# 6502_BASIC.net
KiCad netlist of a schematic drawn in EAGLE
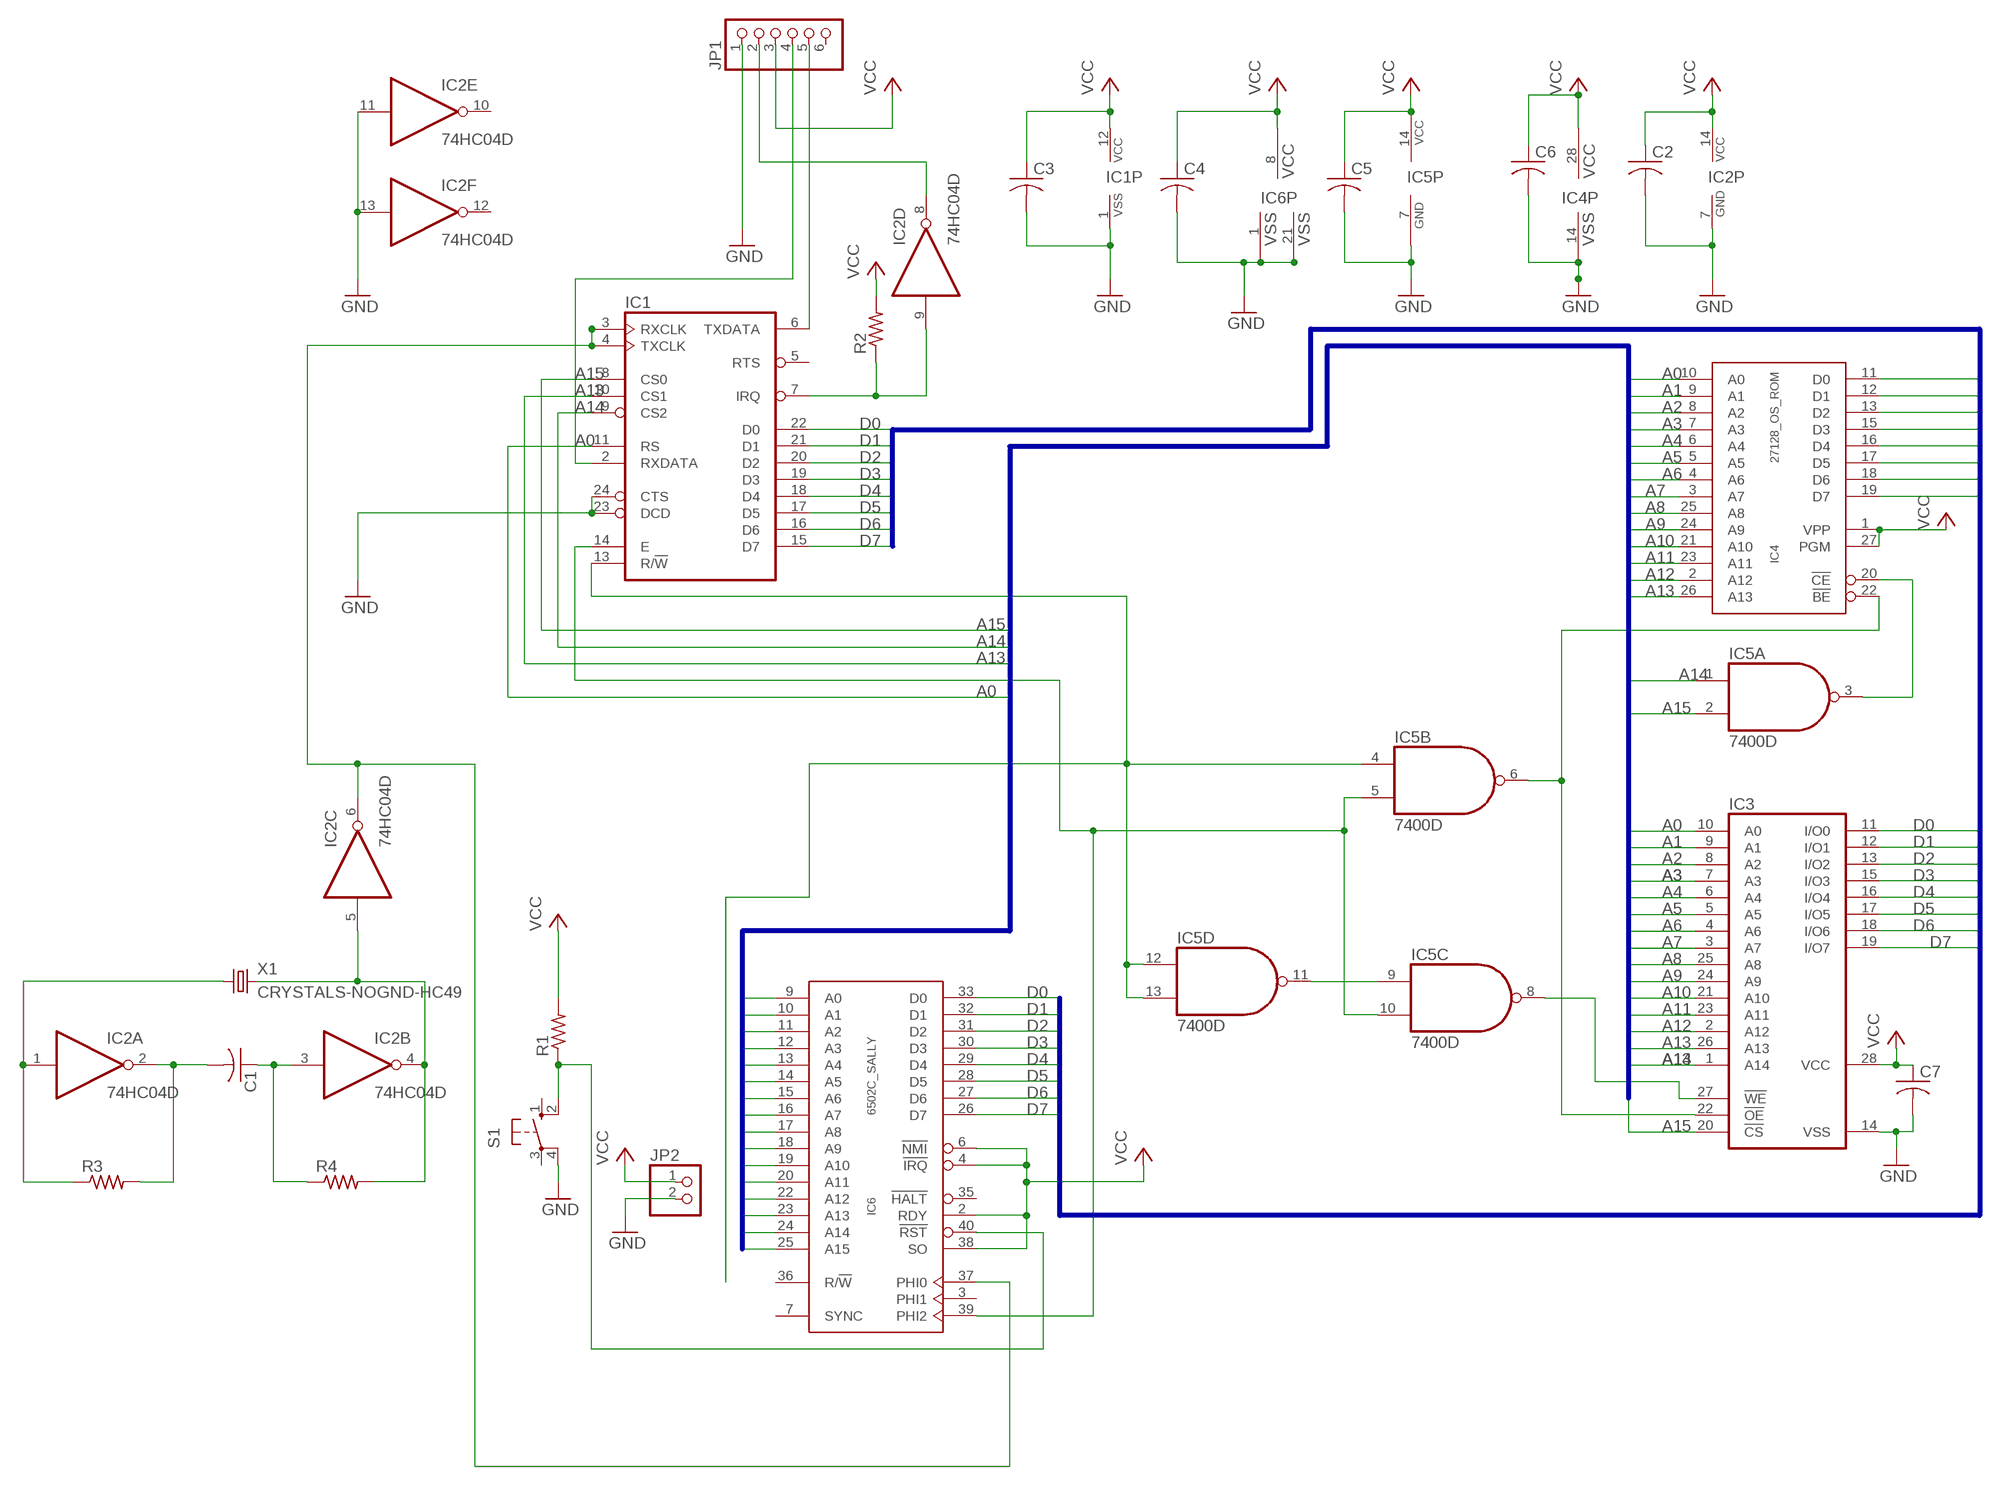
[diagram p0: schematic, sheet 1]

(export (version "E")
  (design (tool "Eeschema 10.0.6"))
  (components
    (comp (ref "C1")
      (value "C-USC1608")
      (footprint "eagle-import:C1608")
      (libsource (lib "eagle-import") (part "C-USC1608"))
    )
    (comp (ref "C2")
      (value "C-USC1608")
      (footprint "eagle-import:C1608")
      (libsource (lib "eagle-import") (part "C-USC1608"))
    )
    (comp (ref "C3")
      (value "C-USC1608")
      (footprint "eagle-import:C1608")
      (libsource (lib "eagle-import") (part "C-USC1608"))
    )
    (comp (ref "C4")
      (value "C-USC1608")
      (footprint "eagle-import:C1608")
      (libsource (lib "eagle-import") (part "C-USC1608"))
    )
    (comp (ref "C5")
      (value "C-USC1608")
      (footprint "eagle-import:C1608")
      (libsource (lib "eagle-import") (part "C-USC1608"))
    )
    (comp (ref "C6")
      (value "C-USC1608")
      (footprint "eagle-import:C1608")
      (libsource (lib "eagle-import") (part "C-USC1608"))
    )
    (comp (ref "C7")
      (value "C-USC1608")
      (footprint "eagle-import:C1608")
      (libsource (lib "eagle-import") (part "C-USC1608"))
    )
    (comp (ref "IC1")
      (value "6850")
      (footprint "eagle-import:DIL24")
      (fields (field (name "MF") "NTE ELECTRONICS") (field (name "MPN") "NTE6850"))
      (libsource (lib "eagle-import") (part "6850"))
    )
    (comp (ref "IC2")
      (value "74HC04D")
      (footprint "eagle-import:SO14")
      (libsource (lib "eagle-import") (part "7404DHC"))
    )
    (comp (ref "IC3")
      (value "62256P")
      (footprint "eagle-import:DIL28-6")
      (libsource (lib "eagle-import") (part "62256P"))
    )
    (comp (ref "IC4")
      (value "27128_OS_ROM")
      (footprint "eagle-import:DIL28")
      (libsource (lib "eagle-import") (part "27128_OS_ROM"))
    )
    (comp (ref "IC5")
      (value "7400D")
      (footprint "eagle-import:SO14")
      (libsource (lib "eagle-import") (part "7400D"))
    )
    (comp (ref "IC6")
      (value "6502C_SALLY")
      (footprint "eagle-import:DIL40")
      (libsource (lib "eagle-import") (part "6502C_SALLY"))
    )
    (comp (ref "JP1")
      (value "HEADER-1X6")
      (footprint "eagle-import:1X06_OVAL")
      (libsource (lib "eagle-import") (part "HEADER-1X6"))
    )
    (comp (ref "JP2")
      (value "HEADER-1X2")
      (footprint "eagle-import:1X02_OVAL")
      (libsource (lib "eagle-import") (part "HEADER-1X2"))
    )
    (comp (ref "R1")
      (value "R-US_R0603")
      (footprint "eagle-import:R0603")
      (libsource (lib "eagle-import") (part "R-US_R0603"))
    )
    (comp (ref "R2")
      (value "R-US_R0603")
      (footprint "eagle-import:R0603")
      (libsource (lib "eagle-import") (part "R-US_R0603"))
    )
    (comp (ref "R3")
      (value "R-US_R0603")
      (footprint "eagle-import:R0603")
      (libsource (lib "eagle-import") (part "R-US_R0603"))
    )
    (comp (ref "R4")
      (value "R-US_R0603")
      (footprint "eagle-import:R0603")
      (libsource (lib "eagle-import") (part "R-US_R0603"))
    )
    (comp (ref "S1")
      (value "10-XX")
      (footprint "eagle-import:B3F-10XX")
      (fields (field (name "MPN") "B3F-1000"))
      (libsource (lib "eagle-import") (part "10-XX"))
    )
    (comp (ref "X1")
      (value "CRYSTALS-NOGND-HC49")
      (footprint "eagle-import:HC49")
      (libsource (lib "eagle-import") (part "CRYSTALS-NOGND-HC49"))
    )
  )
  (nets
    (net (code "1") (name "/A0") (class "Default")
      (node (ref "IC1") (pin "11") (pinfunction "RS_11") (pintype "input"))
      (node (ref "IC3") (pin "10") (pinfunction "A0_10") (pintype "input"))
      (node (ref "IC4") (pin "10") (pinfunction "A0_10") (pintype "input"))
      (node (ref "IC6") (pin "9") (pinfunction "A0_9") (pintype "output"))
    )
    (net (code "2") (name "/A1") (class "Default")
      (node (ref "IC3") (pin "9") (pinfunction "A1_9") (pintype "input"))
      (node (ref "IC4") (pin "9") (pinfunction "A1_9") (pintype "input"))
      (node (ref "IC6") (pin "10") (pinfunction "A1_10") (pintype "output"))
    )
    (net (code "3") (name "/A2") (class "Default")
      (node (ref "IC3") (pin "8") (pinfunction "A2_8") (pintype "input"))
      (node (ref "IC4") (pin "8") (pinfunction "A2_8") (pintype "input"))
      (node (ref "IC6") (pin "11") (pinfunction "A2_11") (pintype "output"))
    )
    (net (code "4") (name "/A3") (class "Default")
      (node (ref "IC3") (pin "7") (pinfunction "A3_7") (pintype "input"))
      (node (ref "IC4") (pin "7") (pinfunction "A3_7") (pintype "input"))
      (node (ref "IC6") (pin "12") (pinfunction "A3_12") (pintype "output"))
    )
    (net (code "5") (name "/A4") (class "Default")
      (node (ref "IC3") (pin "6") (pinfunction "A4_6") (pintype "input"))
      (node (ref "IC4") (pin "6") (pinfunction "A4_6") (pintype "input"))
      (node (ref "IC6") (pin "13") (pinfunction "A4_13") (pintype "output"))
    )
    (net (code "6") (name "/A5") (class "Default")
      (node (ref "IC3") (pin "5") (pinfunction "A5_5") (pintype "input"))
      (node (ref "IC4") (pin "5") (pinfunction "A5_5") (pintype "input"))
      (node (ref "IC6") (pin "14") (pinfunction "A5_14") (pintype "output"))
    )
    (net (code "7") (name "/A6") (class "Default")
      (node (ref "IC3") (pin "4") (pinfunction "A6_4") (pintype "input"))
      (node (ref "IC4") (pin "4") (pinfunction "A6_4") (pintype "input"))
      (node (ref "IC6") (pin "15") (pinfunction "A6_15") (pintype "output"))
    )
    (net (code "8") (name "/A7") (class "Default")
      (node (ref "IC3") (pin "3") (pinfunction "A7_3") (pintype "input"))
      (node (ref "IC4") (pin "3") (pinfunction "A7_3") (pintype "input"))
      (node (ref "IC6") (pin "16") (pinfunction "A7_16") (pintype "output"))
    )
    (net (code "9") (name "/A8") (class "Default")
      (node (ref "IC3") (pin "25") (pinfunction "A8_25") (pintype "input"))
      (node (ref "IC4") (pin "25") (pinfunction "A8_25") (pintype "input"))
      (node (ref "IC6") (pin "17") (pinfunction "A8_17") (pintype "output"))
    )
    (net (code "10") (name "/A9") (class "Default")
      (node (ref "IC3") (pin "24") (pinfunction "A9_24") (pintype "input"))
      (node (ref "IC4") (pin "24") (pinfunction "A9_24") (pintype "input"))
      (node (ref "IC6") (pin "18") (pinfunction "A9_18") (pintype "output"))
    )
    (net (code "11") (name "/A10") (class "Default")
      (node (ref "IC3") (pin "21") (pinfunction "A10_21") (pintype "input"))
      (node (ref "IC4") (pin "21") (pinfunction "A10_21") (pintype "input"))
      (node (ref "IC6") (pin "19") (pinfunction "A10_19") (pintype "output"))
    )
    (net (code "12") (name "/A11") (class "Default")
      (node (ref "IC3") (pin "23") (pinfunction "A11_23") (pintype "input"))
      (node (ref "IC4") (pin "23") (pinfunction "A11_23") (pintype "input"))
      (node (ref "IC6") (pin "20") (pinfunction "A11_20") (pintype "output"))
    )
    (net (code "13") (name "/A12") (class "Default")
      (node (ref "IC3") (pin "2") (pinfunction "A12_2") (pintype "input"))
      (node (ref "IC4") (pin "2") (pinfunction "A12_2") (pintype "input"))
      (node (ref "IC6") (pin "22") (pinfunction "A12_22") (pintype "output"))
    )
    (net (code "14") (name "/A13") (class "Default")
      (node (ref "IC1") (pin "10") (pinfunction "CS1_10") (pintype "input"))
      (node (ref "IC3") (pin "26") (pinfunction "A13_26") (pintype "input"))
      (node (ref "IC4") (pin "26") (pinfunction "A13_26") (pintype "input"))
      (node (ref "IC6") (pin "23") (pinfunction "A13_23") (pintype "output"))
    )
    (net (code "15") (name "/A14") (class "Default")
      (node (ref "IC1") (pin "9") (pinfunction "CS2_9") (pintype "input"))
      (node (ref "IC3") (pin "1") (pinfunction "A14_1") (pintype "input"))
      (node (ref "IC5") (pin "1") (pinfunction "I0_1") (pintype "input"))
      (node (ref "IC6") (pin "24") (pinfunction "A14_24") (pintype "output"))
    )
    (net (code "16") (name "/A15") (class "Default")
      (node (ref "IC1") (pin "8") (pinfunction "CS0_8") (pintype "input"))
      (node (ref "IC3") (pin "20") (pinfunction "~{CS}_20") (pintype "input"))
      (node (ref "IC5") (pin "2") (pinfunction "I1_2") (pintype "input"))
      (node (ref "IC6") (pin "25") (pinfunction "A15_25") (pintype "output"))
    )
    (net (code "17") (name "/D0") (class "Default")
      (node (ref "IC1") (pin "22") (pinfunction "D0_22") (pintype "bidirectional"))
      (node (ref "IC3") (pin "11") (pinfunction "I/O0_11") (pintype "bidirectional"))
      (node (ref "IC4") (pin "11") (pinfunction "D0_11") (pintype "output"))
      (node (ref "IC6") (pin "33") (pinfunction "D0_33") (pintype "bidirectional"))
    )
    (net (code "18") (name "/D1") (class "Default")
      (node (ref "IC1") (pin "21") (pinfunction "D1_21") (pintype "bidirectional"))
      (node (ref "IC3") (pin "12") (pinfunction "I/O1_12") (pintype "bidirectional"))
      (node (ref "IC4") (pin "12") (pinfunction "D1_12") (pintype "output"))
      (node (ref "IC6") (pin "32") (pinfunction "D1_32") (pintype "bidirectional"))
    )
    (net (code "19") (name "/D2") (class "Default")
      (node (ref "IC1") (pin "20") (pinfunction "D2_20") (pintype "bidirectional"))
      (node (ref "IC3") (pin "13") (pinfunction "I/O2_13") (pintype "bidirectional"))
      (node (ref "IC4") (pin "13") (pinfunction "D2_13") (pintype "output"))
      (node (ref "IC6") (pin "31") (pinfunction "D2_31") (pintype "bidirectional"))
    )
    (net (code "20") (name "/D3") (class "Default")
      (node (ref "IC1") (pin "19") (pinfunction "D3_19") (pintype "bidirectional"))
      (node (ref "IC3") (pin "15") (pinfunction "I/O3_15") (pintype "bidirectional"))
      (node (ref "IC4") (pin "15") (pinfunction "D3_15") (pintype "output"))
      (node (ref "IC6") (pin "30") (pinfunction "D3_30") (pintype "bidirectional"))
    )
    (net (code "21") (name "/D4") (class "Default")
      (node (ref "IC1") (pin "18") (pinfunction "D4_18") (pintype "bidirectional"))
      (node (ref "IC3") (pin "16") (pinfunction "I/O4_16") (pintype "bidirectional"))
      (node (ref "IC4") (pin "16") (pinfunction "D4_16") (pintype "output"))
      (node (ref "IC6") (pin "29") (pinfunction "D4_29") (pintype "bidirectional"))
    )
    (net (code "22") (name "/D5") (class "Default")
      (node (ref "IC1") (pin "17") (pinfunction "D5_17") (pintype "bidirectional"))
      (node (ref "IC3") (pin "17") (pinfunction "I/O5_17") (pintype "bidirectional"))
      (node (ref "IC4") (pin "17") (pinfunction "D5_17") (pintype "output"))
      (node (ref "IC6") (pin "28") (pinfunction "D5_28") (pintype "bidirectional"))
    )
    (net (code "23") (name "/D6") (class "Default")
      (node (ref "IC1") (pin "16") (pinfunction "D6_16") (pintype "bidirectional"))
      (node (ref "IC3") (pin "18") (pinfunction "I/O6_18") (pintype "bidirectional"))
      (node (ref "IC4") (pin "18") (pinfunction "D6_18") (pintype "output"))
      (node (ref "IC6") (pin "27") (pinfunction "D6_27") (pintype "bidirectional"))
    )
    (net (code "24") (name "/D7") (class "Default")
      (node (ref "IC1") (pin "15") (pinfunction "D7_15") (pintype "bidirectional"))
      (node (ref "IC3") (pin "19") (pinfunction "I/O7_19") (pintype "bidirectional"))
      (node (ref "IC4") (pin "19") (pinfunction "D7_19") (pintype "output"))
      (node (ref "IC6") (pin "26") (pinfunction "D7_26") (pintype "bidirectional"))
    )
    (net (code "25") (name "GND") (class "Default")
      (node (ref "C2") (pin "2") (pinfunction "2_2") (pintype "passive"))
      (node (ref "C3") (pin "2") (pinfunction "2_2") (pintype "passive"))
      (node (ref "C4") (pin "2") (pinfunction "2_2") (pintype "passive"))
      (node (ref "C5") (pin "2") (pinfunction "2_2") (pintype "passive"))
      (node (ref "C6") (pin "2") (pinfunction "2_2") (pintype "passive"))
      (node (ref "C7") (pin "2") (pinfunction "2_2") (pintype "passive"))
      (node (ref "IC1") (pin "1") (pinfunction "VSS_1") (pintype "power_in"))
      (node (ref "IC1") (pin "23") (pinfunction "DCD_23") (pintype "input"))
      (node (ref "IC1") (pin "24") (pinfunction "CTS_24") (pintype "input"))
      (node (ref "IC2") (pin "11") (pinfunction "I_11") (pintype "input"))
      (node (ref "IC2") (pin "13") (pinfunction "I_13") (pintype "input"))
      (node (ref "IC2") (pin "7") (pinfunction "GND_7") (pintype "power_in"))
      (node (ref "IC3") (pin "14") (pinfunction "VSS_14") (pintype "power_in"))
      (node (ref "IC4") (pin "14") (pinfunction "VSS_14") (pintype "power_in"))
      (node (ref "IC5") (pin "7") (pinfunction "GND_7") (pintype "power_in"))
      (node (ref "IC6") (pin "1") (pinfunction "VSS_1") (pintype "power_in"))
      (node (ref "IC6") (pin "21") (pinfunction "VSS1_21") (pintype "power_in"))
      (node (ref "JP1") (pin "1") (pinfunction "1_1") (pintype "passive"))
      (node (ref "JP2") (pin "2") (pinfunction "2_2") (pintype "passive"))
      (node (ref "S1") (pin "4") (pinfunction "P1_4") (pintype "passive"))
    )
    (net (code "26") (name "Net-(IC1A-E)") (class "Default")
      (node (ref "IC1") (pin "14") (pinfunction "E_14") (pintype "input"))
      (node (ref "IC5") (pin "10") (pinfunction "I1_10") (pintype "input"))
      (node (ref "IC5") (pin "5") (pinfunction "I1_5") (pintype "input"))
      (node (ref "IC6") (pin "39") (pinfunction "PHI2_39") (pintype "output"))
    )
    (net (code "27") (name "Net-(IC1A-IRQ)") (class "Default")
      (node (ref "IC1") (pin "7") (pinfunction "IRQ_7") (pintype "output"))
      (node (ref "IC2") (pin "9") (pinfunction "I_9") (pintype "input"))
      (node (ref "R2") (pin "1") (pinfunction "1_1") (pintype "passive"))
    )
    (net (code "28") (name "Net-(IC1A-RXCLK)") (class "Default")
      (node (ref "IC1") (pin "3") (pinfunction "RXCLK_3") (pintype "input"))
      (node (ref "IC1") (pin "4") (pinfunction "TXCLK_4") (pintype "input"))
      (node (ref "IC2") (pin "6") (pinfunction "O_6") (pintype "output"))
      (node (ref "IC6") (pin "37") (pinfunction "PHI0_37") (pintype "input"))
    )
    (net (code "29") (name "Net-(IC1A-RXDATA)") (class "Default")
      (node (ref "IC1") (pin "2") (pinfunction "RXDATA_2") (pintype "input"))
      (node (ref "JP1") (pin "4") (pinfunction "4_4") (pintype "passive"))
    )
    (net (code "30") (name "Net-(IC1A-R{slash}~{W})") (class "Default")
      (node (ref "IC1") (pin "13") (pinfunction "R/~{W}_13") (pintype "input"))
      (node (ref "IC5") (pin "12") (pinfunction "I0_12") (pintype "input"))
      (node (ref "IC5") (pin "13") (pinfunction "I1_13") (pintype "input"))
      (node (ref "IC5") (pin "4") (pinfunction "I0_4") (pintype "input"))
    )
    (net (code "31") (name "Net-(IC1A-TXDATA)") (class "Default")
      (node (ref "IC1") (pin "6") (pinfunction "TXDATA_6") (pintype "output"))
      (node (ref "JP1") (pin "5") (pinfunction "5_5") (pintype "passive"))
    )
    (net (code "32") (name "Net-(IC2A-I)") (class "Default")
      (node (ref "IC2") (pin "1") (pinfunction "I_1") (pintype "input"))
      (node (ref "R3") (pin "1") (pinfunction "1_1") (pintype "passive"))
      (node (ref "X1") (pin "1") (pinfunction "1_1") (pintype "passive"))
    )
    (net (code "33") (name "Net-(IC2A-O)") (class "Default")
      (node (ref "C1") (pin "2") (pinfunction "2_2") (pintype "passive"))
      (node (ref "IC2") (pin "2") (pinfunction "O_2") (pintype "output"))
      (node (ref "R3") (pin "2") (pinfunction "2_2") (pintype "passive"))
    )
    (net (code "34") (name "Net-(IC2B-I)") (class "Default")
      (node (ref "C1") (pin "1") (pinfunction "1_1") (pintype "passive"))
      (node (ref "IC2") (pin "3") (pinfunction "I_3") (pintype "input"))
      (node (ref "R4") (pin "1") (pinfunction "1_1") (pintype "passive"))
    )
    (net (code "35") (name "Net-(IC2B-O)") (class "Default")
      (node (ref "IC2") (pin "4") (pinfunction "O_4") (pintype "output"))
      (node (ref "IC2") (pin "5") (pinfunction "I_5") (pintype "input"))
      (node (ref "R4") (pin "2") (pinfunction "2_2") (pintype "passive"))
      (node (ref "X1") (pin "2") (pinfunction "2_2") (pintype "passive"))
    )
    (net (code "36") (name "Net-(IC2D-O)") (class "Default")
      (node (ref "IC2") (pin "8") (pinfunction "O_8") (pintype "output"))
      (node (ref "JP1") (pin "2") (pinfunction "2_2") (pintype "passive"))
    )
    (net (code "37") (name "Net-(IC3-~{OE})") (class "Default")
      (node (ref "IC3") (pin "22") (pinfunction "~{OE}_22") (pintype "input"))
      (node (ref "IC4") (pin "22") (pinfunction "~{BE}_22") (pintype "input"))
      (node (ref "IC5") (pin "6") (pinfunction "O_6") (pintype "output"))
    )
    (net (code "38") (name "Net-(IC3-~{WE})") (class "Default")
      (node (ref "IC3") (pin "27") (pinfunction "~{WE}_27") (pintype "input"))
      (node (ref "IC5") (pin "8") (pinfunction "O_8") (pintype "output"))
    )
    (net (code "39") (name "Net-(IC4A-~{CE})") (class "Default")
      (node (ref "IC4") (pin "20") (pinfunction "~{CE}_20") (pintype "input"))
      (node (ref "IC5") (pin "3") (pinfunction "O_3") (pintype "output"))
    )
    (net (code "40") (name "Net-(IC5C-I0)") (class "Default")
      (node (ref "IC5") (pin "11") (pinfunction "O_11") (pintype "output"))
      (node (ref "IC5") (pin "9") (pinfunction "I0_9") (pintype "input"))
    )
    (net (code "41") (name "Net-(IC6A-~{RST})") (class "Default")
      (node (ref "IC6") (pin "40") (pinfunction "~{RST}_40") (pintype "input"))
      (node (ref "R1") (pin "1") (pinfunction "1_1") (pintype "passive"))
      (node (ref "S1") (pin "2") (pinfunction "S1_2") (pintype "passive"))
    )
    (net (code "42") (name "VCC") (class "Default")
      (node (ref "C2") (pin "1") (pinfunction "1_1") (pintype "passive"))
      (node (ref "C3") (pin "1") (pinfunction "1_1") (pintype "passive"))
      (node (ref "C4") (pin "1") (pinfunction "1_1") (pintype "passive"))
      (node (ref "C5") (pin "1") (pinfunction "1_1") (pintype "passive"))
      (node (ref "C6") (pin "1") (pinfunction "1_1") (pintype "passive"))
      (node (ref "C7") (pin "1") (pinfunction "1_1") (pintype "passive"))
      (node (ref "IC1") (pin "12") (pinfunction "VCC_12") (pintype "power_in"))
      (node (ref "IC2") (pin "14") (pinfunction "VCC_14") (pintype "power_in"))
      (node (ref "IC3") (pin "28") (pinfunction "VCC_28") (pintype "power_in"))
      (node (ref "IC4") (pin "1") (pinfunction "VPP_1") (pintype "input"))
      (node (ref "IC4") (pin "27") (pinfunction "PGM_27") (pintype "input"))
      (node (ref "IC4") (pin "28") (pinfunction "VCC_28") (pintype "power_in"))
      (node (ref "IC5") (pin "14") (pinfunction "VCC_14") (pintype "power_in"))
      (node (ref "IC6") (pin "2") (pinfunction "RDY_2") (pintype "input"))
      (node (ref "IC6") (pin "38") (pinfunction "SO_38") (pintype "input"))
      (node (ref "IC6") (pin "4") (pinfunction "~{IRQ}_4") (pintype "input"))
      (node (ref "IC6") (pin "6") (pinfunction "~{NMI}_6") (pintype "input"))
      (node (ref "IC6") (pin "8") (pinfunction "VCC_8") (pintype "power_in"))
      (node (ref "JP1") (pin "3") (pinfunction "3_3") (pintype "passive"))
      (node (ref "JP2") (pin "1") (pinfunction "1_1") (pintype "passive"))
      (node (ref "R1") (pin "2") (pinfunction "2_2") (pintype "passive"))
      (node (ref "R2") (pin "2") (pinfunction "2_2") (pintype "passive"))
    )
    (net (code "43") (name "unconnected-(IC1A-RTS-Pad5)") (class "Default")
      (node (ref "IC1") (pin "5") (pinfunction "RTS_5") (pintype "output"))
    )
    (net (code "44") (name "unconnected-(IC2E-O-Pad10)") (class "Default")
      (node (ref "IC2") (pin "10") (pinfunction "O_10") (pintype "output"))
    )
    (net (code "45") (name "unconnected-(IC2F-O-Pad12)") (class "Default")
      (node (ref "IC2") (pin "12") (pinfunction "O_12") (pintype "output"))
    )
    (net (code "46") (name "unconnected-(IC6A-PHI1-Pad3)") (class "Default")
      (node (ref "IC6") (pin "3") (pinfunction "PHI1_3") (pintype "output"))
    )
    (net (code "47") (name "unconnected-(IC6A-R{slash}~{W}-Pad36)") (class "Default")
      (node (ref "IC6") (pin "36") (pinfunction "R/~{W}_36") (pintype "output"))
    )
    (net (code "48") (name "unconnected-(IC6A-SYNC-Pad7)") (class "Default")
      (node (ref "IC6") (pin "7") (pinfunction "SYNC_7") (pintype "output"))
    )
    (net (code "49") (name "unconnected-(IC6A-~{HALT}-Pad35)") (class "Default")
      (node (ref "IC6") (pin "35") (pinfunction "~{HALT}_35") (pintype "input"))
    )
    (net (code "50") (name "unconnected-(JP1-Pad6)") (class "Default")
      (node (ref "JP1") (pin "6") (pinfunction "6_6") (pintype "passive"))
    )
    (net (code "51") (name "unconnected-(S1-P-Pad3)") (class "Default")
      (node (ref "S1") (pin "3") (pinfunction "P_3") (pintype "passive"))
    )
    (net (code "52") (name "unconnected-(S1-S-Pad1)") (class "Default")
      (node (ref "S1") (pin "1") (pinfunction "S_1") (pintype "passive"))
    )
  )
)
